# BMI160.net
KiCad netlist of a schematic drawn in Altium Designer
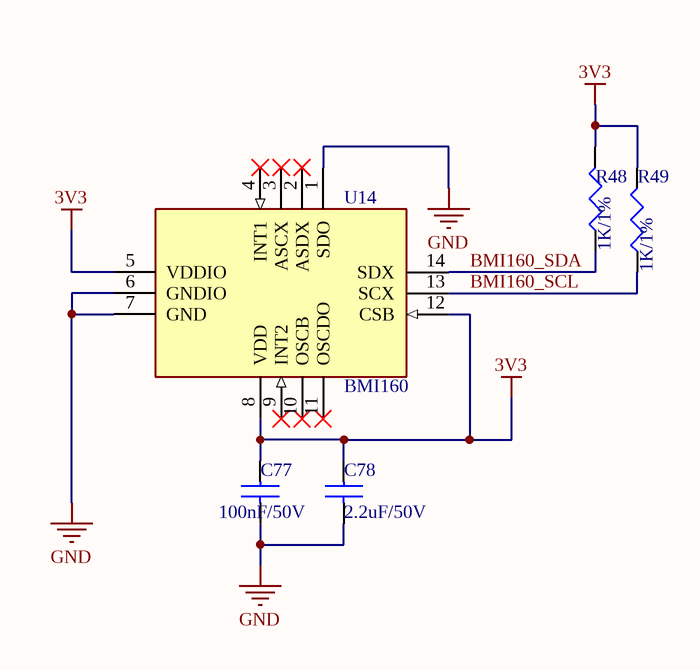
[diagram p0: BMI160.SchDoc]

(export (version "E")
  (design (tool "Eeschema 10.0.6"))
  (components
    (comp (ref "C77") (value "100nF/50V") (footprint "C0402") (libsource (lib "*") (part "CAP NP")))
    (comp (ref "C78") (value "2.2uF/50V") (footprint "C0402") (libsource (lib "*") (part "CAP NP")))
    (comp (ref "R48") (value "1K/1%") (footprint "R0402") (libsource (lib "*") (part "RESISTOR")))
    (comp (ref "R49") (value "1K/1%") (footprint "R0402") (libsource (lib "*") (part "RESISTOR")))
    (comp (ref "U14")
      (value "BMI160")
      (footprint "PQFN50P300X250X88-14N")
      (description "Integrated Circuit")
      (fields (field (name "MOUSER PART NUMBER") "262-BMI160"))
      (libsource (lib "VESC_DEVICE_Library") (part "BMI160"))
    )
  )
  (nets
    (net (code "1") (name "/BMI160_SCL") (class "Default")
      (node (ref "R49") (pin "1") (pinfunction "1_1") (pintype "passive"))
      (node (ref "U14") (pin "13") (pinfunction "SCX_13") (pintype "passive"))
    )
    (net (code "2") (name "/BMI160_SDA") (class "Default")
      (node (ref "R48") (pin "1") (pinfunction "1_1") (pintype "passive"))
      (node (ref "U14") (pin "14") (pinfunction "SDX_14") (pintype "passive"))
    )
    (net (code "3") (name "3V3") (class "Default")
      (node (ref "C77") (pin "1") (pinfunction "1_1") (pintype "passive"))
      (node (ref "C78") (pin "1") (pinfunction "1_1") (pintype "passive"))
      (node (ref "R48") (pin "2") (pinfunction "2_2") (pintype "passive"))
      (node (ref "R49") (pin "2") (pinfunction "2_2") (pintype "passive"))
      (node (ref "U14") (pin "12") (pinfunction "CSB_12") (pintype "input"))
      (node (ref "U14") (pin "5") (pinfunction "VDDIO_5") (pintype "power_in"))
      (node (ref "U14") (pin "8") (pinfunction "VDD_8") (pintype "power_in"))
    )
    (net (code "4") (name "GND") (class "Default")
      (node (ref "C77") (pin "2") (pinfunction "2_2") (pintype "passive"))
      (node (ref "C78") (pin "2") (pinfunction "2_2") (pintype "passive"))
      (node (ref "U14") (pin "1") (pinfunction "SDO_1") (pintype "passive"))
      (node (ref "U14") (pin "6") (pinfunction "GNDIO_6") (pintype "power_in"))
      (node (ref "U14") (pin "7") (pinfunction "GND_7") (pintype "power_in"))
    )
    (net (code "5") (name "unconnected-(U14-ASCX-Pad3)") (class "Default")
      (node (ref "U14") (pin "3") (pinfunction "ASCX_3") (pintype "passive+no_connect"))
    )
    (net (code "6") (name "unconnected-(U14-ASDX-Pad2)") (class "Default")
      (node (ref "U14") (pin "2") (pinfunction "ASDX_2") (pintype "passive+no_connect"))
    )
    (net (code "7") (name "unconnected-(U14-INT1-Pad4)") (class "Default")
      (node (ref "U14") (pin "4") (pinfunction "INT1_4") (pintype "input+no_connect"))
    )
    (net (code "8") (name "unconnected-(U14-INT2-Pad9)") (class "Default")
      (node (ref "U14") (pin "9") (pinfunction "INT2_9") (pintype "input+no_connect"))
    )
    (net (code "9") (name "unconnected-(U14-OSCB-Pad10)") (class "Default")
      (node (ref "U14") (pin "10") (pinfunction "OSCB_10") (pintype "passive+no_connect"))
    )
    (net (code "10") (name "unconnected-(U14-OSCDO-Pad11)") (class "Default")
      (node (ref "U14") (pin "11") (pinfunction "OSCDO_11") (pintype "passive+no_connect"))
    )
  )
)
